# 1-Schematic_PCBTASK.net
KiCad netlist of a schematic drawn in EasyEDA
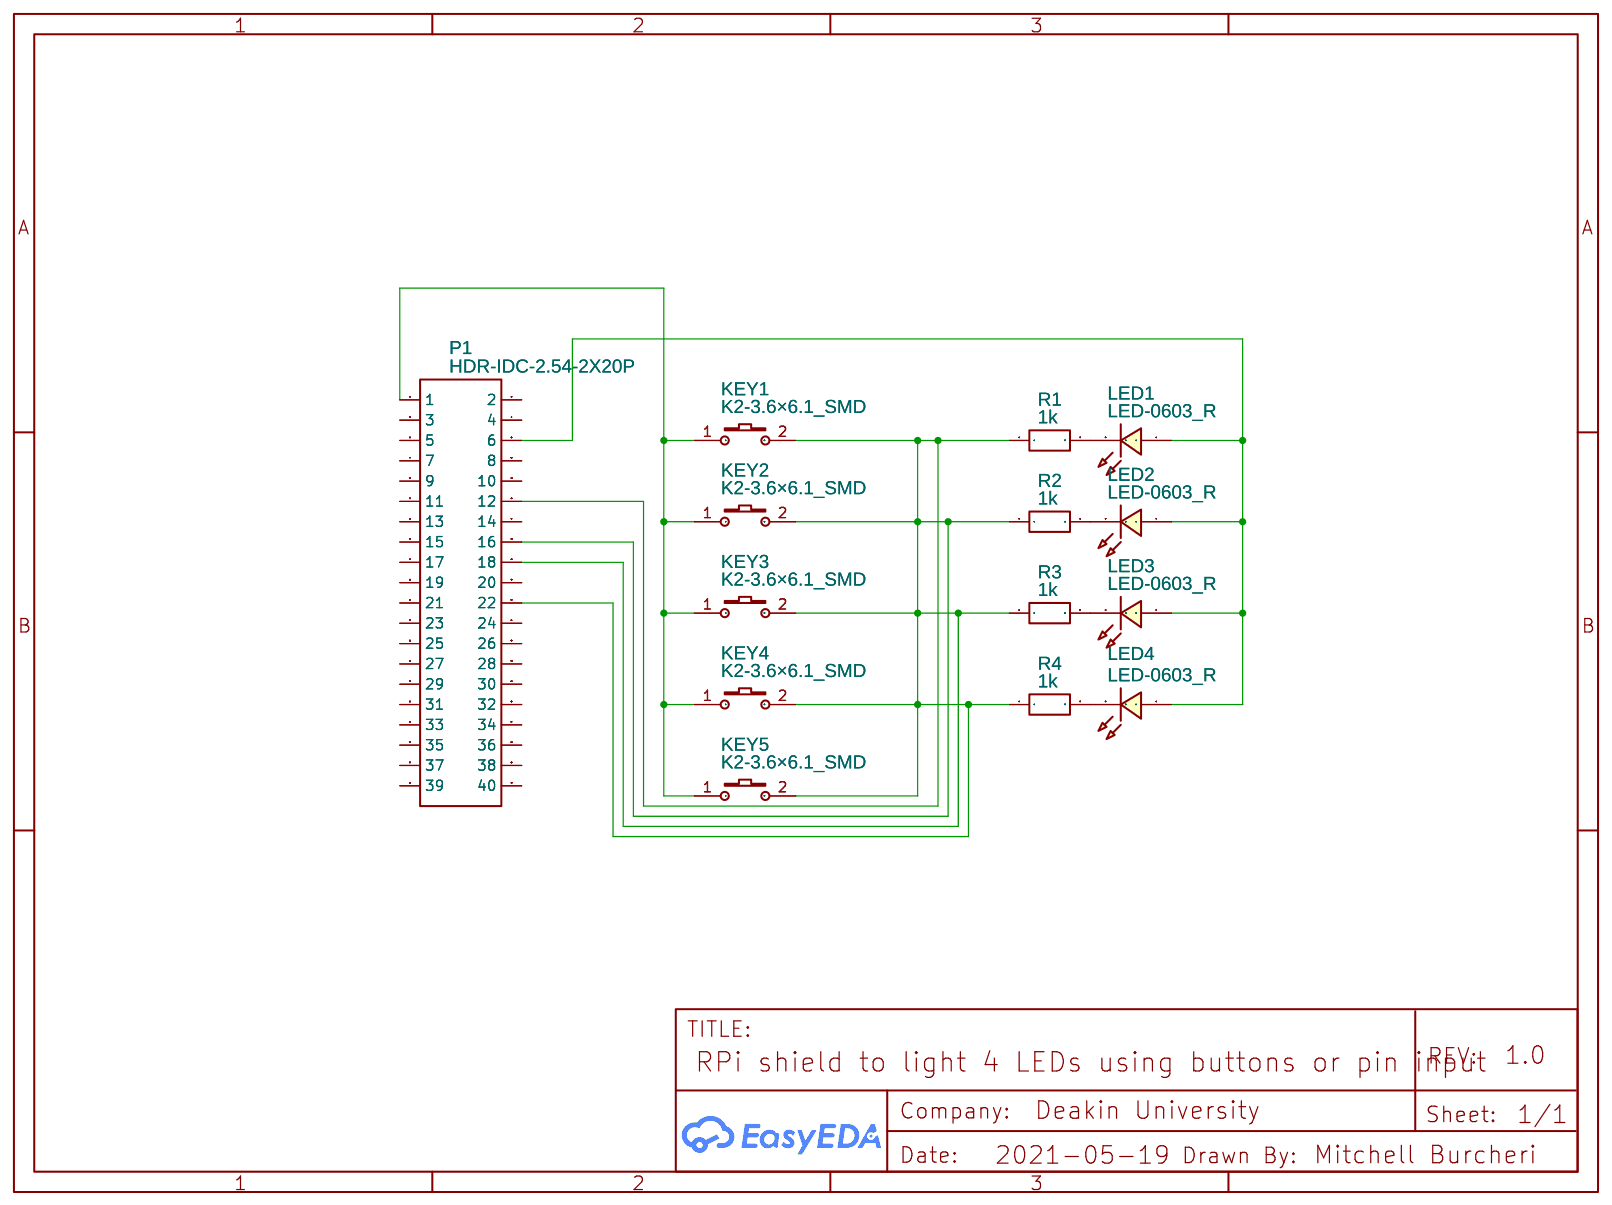
[diagram p0: schematic sheet]

(export (version "E")
  (design (tool "Eeschema 10.0.6"))
  (components
    (comp (ref "KEY1")
      (value "K2-3.6×6.1_SMD")
      (fields
        (field (name "BOM_Manufacturer Part") "K2-1107ST-A4SW-06")
        (field (name "BOM_Supplier Part") "C118141")
      )
      (libsource (lib "") (part "K2-3.6×6.1_SMD"))
    )
    (comp (ref "KEY2")
      (value "K2-3.6×6.1_SMD")
      (fields
        (field (name "BOM_Manufacturer Part") "K2-1107ST-A4SW-06")
        (field (name "BOM_Supplier Part") "C118141")
      )
      (libsource (lib "") (part "K2-3.6×6.1_SMD"))
    )
    (comp (ref "KEY3")
      (value "K2-3.6×6.1_SMD")
      (fields
        (field (name "BOM_Manufacturer Part") "K2-1107ST-A4SW-06")
        (field (name "BOM_Supplier Part") "C118141")
      )
      (libsource (lib "") (part "K2-3.6×6.1_SMD"))
    )
    (comp (ref "KEY4")
      (value "K2-3.6×6.1_SMD")
      (fields
        (field (name "BOM_Manufacturer Part") "K2-1107ST-A4SW-06")
        (field (name "BOM_Supplier Part") "C118141")
      )
      (libsource (lib "") (part "K2-3.6×6.1_SMD"))
    )
    (comp (ref "KEY5")
      (value "K2-3.6×6.1_SMD")
      (fields
        (field (name "BOM_Manufacturer Part") "K2-1107ST-A4SW-06")
        (field (name "BOM_Supplier Part") "C118141")
      )
      (libsource (lib "") (part "K2-3.6×6.1_SMD"))
    )
    (comp (ref "LED1")
      (value "LED-0603_R")
      (fields
        (field (name "BOM_Manufacturer Part") "19-217/R6C-AL1M2VY/3T")
        (field (name "BOM_Supplier Part") "C72044")
      )
      (libsource (lib "") (part "LED-0603_R"))
    )
    (comp (ref "LED2")
      (value "LED-0603_R")
      (fields
        (field (name "BOM_Manufacturer Part") "19-217/R6C-AL1M2VY/3T")
        (field (name "BOM_Supplier Part") "C72044")
      )
      (libsource (lib "") (part "LED-0603_R"))
    )
    (comp (ref "LED3")
      (value "LED-0603_R")
      (fields
        (field (name "BOM_Manufacturer Part") "19-217/R6C-AL1M2VY/3T")
        (field (name "BOM_Supplier Part") "C72044")
      )
      (libsource (lib "") (part "LED-0603_R"))
    )
    (comp (ref "LED4")
      (value "LED-0603_R")
      (fields
        (field (name "BOM_Manufacturer Part") "19-217/R6C-AL1M2VY/3T")
        (field (name "BOM_Supplier Part") "C72044")
      )
      (libsource (lib "") (part "LED-0603_R"))
    )
    (comp (ref "P1")
      (value "HDR-IDC-2.54-2X20P")
      (fields
        (field (name "BOM_Manufacturer Part") "IDC Box 2X20 2.54MM")
        (field (name "BOM_Supplier Part") "C9138")
      )
      (libsource (lib "") (part "HDR-IDC-2.54-2X20P"))
    )
    (comp (ref "R1") (value "1k") (libsource (lib "") (part "R_0201_EU")))
    (comp (ref "R2") (value "1k") (libsource (lib "") (part "R_0201_EU")))
    (comp (ref "R3") (value "1k") (libsource (lib "") (part "R_0201_EU")))
    (comp (ref "R4") (value "1k") (libsource (lib "") (part "R_0201_EU")))
  )
  (nets
    (net (code "1") (name "Net-(KEY1-Pad1)") (class "Default")
      (node (ref "KEY1") (pin "1") (pinfunction "1_1") (pintype "unspecified"))
      (node (ref "KEY2") (pin "1") (pinfunction "1_1") (pintype "unspecified"))
      (node (ref "KEY3") (pin "1") (pinfunction "1_1") (pintype "unspecified"))
      (node (ref "KEY4") (pin "1") (pinfunction "1_1") (pintype "unspecified"))
      (node (ref "KEY5") (pin "1") (pinfunction "1_1") (pintype "unspecified"))
      (node (ref "P1") (pin "1") (pinfunction "1_1") (pintype "unspecified"))
    )
    (net (code "2") (name "Net-(KEY1-Pad2)") (class "Default")
      (node (ref "KEY1") (pin "2") (pinfunction "2_2") (pintype "unspecified"))
      (node (ref "KEY2") (pin "2") (pinfunction "2_2") (pintype "unspecified"))
      (node (ref "KEY3") (pin "2") (pinfunction "2_2") (pintype "unspecified"))
      (node (ref "KEY4") (pin "2") (pinfunction "2_2") (pintype "unspecified"))
      (node (ref "KEY5") (pin "2") (pinfunction "2_2") (pintype "unspecified"))
      (node (ref "P1") (pin "12") (pinfunction "12_12") (pintype "unspecified"))
      (node (ref "P1") (pin "16") (pinfunction "16_16") (pintype "unspecified"))
      (node (ref "P1") (pin "18") (pinfunction "18_18") (pintype "unspecified"))
      (node (ref "P1") (pin "22") (pinfunction "22_22") (pintype "unspecified"))
      (node (ref "R1") (pin "1") (pinfunction "1_1") (pintype "unspecified"))
      (node (ref "R2") (pin "1") (pinfunction "1_1") (pintype "unspecified"))
      (node (ref "R3") (pin "1") (pinfunction "1_1") (pintype "unspecified"))
      (node (ref "R4") (pin "1") (pinfunction "1_1") (pintype "unspecified"))
    )
    (net (code "3") (name "Net-(LED1-Pad1)") (class "Default")
      (node (ref "LED1") (pin "1") (pinfunction "1_1") (pintype "unspecified"))
      (node (ref "LED2") (pin "1") (pinfunction "1_1") (pintype "unspecified"))
      (node (ref "LED3") (pin "1") (pinfunction "1_1") (pintype "unspecified"))
      (node (ref "LED4") (pin "1") (pinfunction "1_1") (pintype "unspecified"))
      (node (ref "P1") (pin "6") (pinfunction "6_6") (pintype "unspecified"))
    )
    (net (code "4") (name "Net-(LED1-Pad2)") (class "Default")
      (node (ref "LED1") (pin "2") (pinfunction "2_2") (pintype "unspecified"))
      (node (ref "R1") (pin "2") (pinfunction "2_2") (pintype "unspecified"))
    )
    (net (code "5") (name "Net-(LED2-Pad2)") (class "Default")
      (node (ref "LED2") (pin "2") (pinfunction "2_2") (pintype "unspecified"))
      (node (ref "R2") (pin "2") (pinfunction "2_2") (pintype "unspecified"))
    )
    (net (code "6") (name "Net-(LED3-Pad2)") (class "Default")
      (node (ref "LED3") (pin "2") (pinfunction "2_2") (pintype "unspecified"))
      (node (ref "R3") (pin "2") (pinfunction "2_2") (pintype "unspecified"))
    )
    (net (code "7") (name "Net-(LED4-Pad2)") (class "Default")
      (node (ref "LED4") (pin "2") (pinfunction "2_2") (pintype "unspecified"))
      (node (ref "R4") (pin "2") (pinfunction "2_2") (pintype "unspecified"))
    )
    (net (code "8") (name "unconnected-(P1-Pad2)") (class "Default")
      (node (ref "P1") (pin "2") (pinfunction "2_2") (pintype "unspecified"))
    )
    (net (code "9") (name "unconnected-(P1-Pad3)") (class "Default")
      (node (ref "P1") (pin "3") (pinfunction "3_3") (pintype "unspecified"))
    )
    (net (code "10") (name "unconnected-(P1-Pad4)") (class "Default")
      (node (ref "P1") (pin "4") (pinfunction "4_4") (pintype "unspecified"))
    )
    (net (code "11") (name "unconnected-(P1-Pad5)") (class "Default")
      (node (ref "P1") (pin "5") (pinfunction "5_5") (pintype "unspecified"))
    )
    (net (code "12") (name "unconnected-(P1-Pad7)") (class "Default")
      (node (ref "P1") (pin "7") (pinfunction "7_7") (pintype "unspecified"))
    )
    (net (code "13") (name "unconnected-(P1-Pad8)") (class "Default")
      (node (ref "P1") (pin "8") (pinfunction "8_8") (pintype "unspecified"))
    )
    (net (code "14") (name "unconnected-(P1-Pad9)") (class "Default")
      (node (ref "P1") (pin "9") (pinfunction "9_9") (pintype "unspecified"))
    )
    (net (code "15") (name "unconnected-(P1-Pad10)") (class "Default")
      (node (ref "P1") (pin "10") (pinfunction "10_10") (pintype "unspecified"))
    )
    (net (code "16") (name "unconnected-(P1-Pad11)") (class "Default")
      (node (ref "P1") (pin "11") (pinfunction "11_11") (pintype "unspecified"))
    )
    (net (code "17") (name "unconnected-(P1-Pad13)") (class "Default")
      (node (ref "P1") (pin "13") (pinfunction "13_13") (pintype "unspecified"))
    )
    (net (code "18") (name "unconnected-(P1-Pad14)") (class "Default")
      (node (ref "P1") (pin "14") (pinfunction "14_14") (pintype "unspecified"))
    )
    (net (code "19") (name "unconnected-(P1-Pad15)") (class "Default")
      (node (ref "P1") (pin "15") (pinfunction "15_15") (pintype "unspecified"))
    )
    (net (code "20") (name "unconnected-(P1-Pad17)") (class "Default")
      (node (ref "P1") (pin "17") (pinfunction "17_17") (pintype "unspecified"))
    )
    (net (code "21") (name "unconnected-(P1-Pad19)") (class "Default")
      (node (ref "P1") (pin "19") (pinfunction "19_19") (pintype "unspecified"))
    )
    (net (code "22") (name "unconnected-(P1-Pad20)") (class "Default")
      (node (ref "P1") (pin "20") (pinfunction "20_20") (pintype "unspecified"))
    )
    (net (code "23") (name "unconnected-(P1-Pad21)") (class "Default")
      (node (ref "P1") (pin "21") (pinfunction "21_21") (pintype "unspecified"))
    )
    (net (code "24") (name "unconnected-(P1-Pad23)") (class "Default")
      (node (ref "P1") (pin "23") (pinfunction "23_23") (pintype "unspecified"))
    )
    (net (code "25") (name "unconnected-(P1-Pad24)") (class "Default")
      (node (ref "P1") (pin "24") (pinfunction "24_24") (pintype "unspecified"))
    )
    (net (code "26") (name "unconnected-(P1-Pad25)") (class "Default")
      (node (ref "P1") (pin "25") (pinfunction "25_25") (pintype "unspecified"))
    )
    (net (code "27") (name "unconnected-(P1-Pad26)") (class "Default")
      (node (ref "P1") (pin "26") (pinfunction "26_26") (pintype "unspecified"))
    )
    (net (code "28") (name "unconnected-(P1-Pad27)") (class "Default")
      (node (ref "P1") (pin "27") (pinfunction "27_27") (pintype "unspecified"))
    )
    (net (code "29") (name "unconnected-(P1-Pad28)") (class "Default")
      (node (ref "P1") (pin "28") (pinfunction "28_28") (pintype "unspecified"))
    )
    (net (code "30") (name "unconnected-(P1-Pad29)") (class "Default")
      (node (ref "P1") (pin "29") (pinfunction "29_29") (pintype "unspecified"))
    )
    (net (code "31") (name "unconnected-(P1-Pad30)") (class "Default")
      (node (ref "P1") (pin "30") (pinfunction "30_30") (pintype "unspecified"))
    )
    (net (code "32") (name "unconnected-(P1-Pad31)") (class "Default")
      (node (ref "P1") (pin "31") (pinfunction "31_31") (pintype "unspecified"))
    )
    (net (code "33") (name "unconnected-(P1-Pad32)") (class "Default")
      (node (ref "P1") (pin "32") (pinfunction "32_32") (pintype "unspecified"))
    )
    (net (code "34") (name "unconnected-(P1-Pad33)") (class "Default")
      (node (ref "P1") (pin "33") (pinfunction "33_33") (pintype "unspecified"))
    )
    (net (code "35") (name "unconnected-(P1-Pad34)") (class "Default")
      (node (ref "P1") (pin "34") (pinfunction "34_34") (pintype "unspecified"))
    )
    (net (code "36") (name "unconnected-(P1-Pad35)") (class "Default")
      (node (ref "P1") (pin "35") (pinfunction "35_35") (pintype "unspecified"))
    )
    (net (code "37") (name "unconnected-(P1-Pad36)") (class "Default")
      (node (ref "P1") (pin "36") (pinfunction "36_36") (pintype "unspecified"))
    )
    (net (code "38") (name "unconnected-(P1-Pad37)") (class "Default")
      (node (ref "P1") (pin "37") (pinfunction "37_37") (pintype "unspecified"))
    )
    (net (code "39") (name "unconnected-(P1-Pad38)") (class "Default")
      (node (ref "P1") (pin "38") (pinfunction "38_38") (pintype "unspecified"))
    )
    (net (code "40") (name "unconnected-(P1-Pad39)") (class "Default")
      (node (ref "P1") (pin "39") (pinfunction "39_39") (pintype "unspecified"))
    )
    (net (code "41") (name "unconnected-(P1-Pad40)") (class "Default")
      (node (ref "P1") (pin "40") (pinfunction "40_40") (pintype "unspecified"))
    )
  )
)
